# Filter-16.net
KiCad netlist of a schematic drawn in Altium Designer
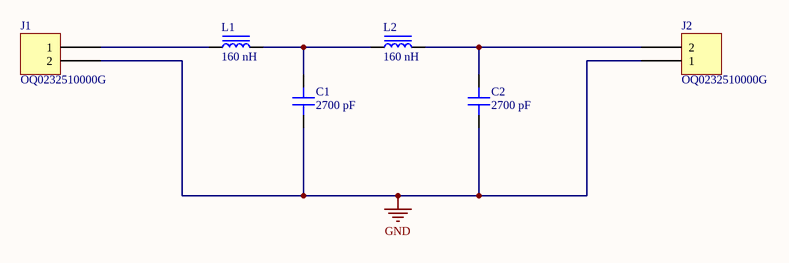
[diagram p0: Filter-16.SchDoc]

(export (version "E")
  (design (tool "Eeschema 10.0.6"))
  (components
    (comp (ref "C1")
      (value "2700 pF")
      (footprint "CAP 0603_1608")
      (description "CAP CER 2700PF 25V NP0 0603")
      (fields (field (name "PART NUMBER") "C0603C272F3GAC7867") (field (name "MANUFACTURER") "KEMET"))
      (libsource (lib "Celestial Altium Library - altium_library") (part "Capacitor"))
    )
    (comp (ref "C2")
      (value "2700 pF")
      (footprint "CAP 0603_1608")
      (description "CAP CER 2700PF 25V NP0 0603")
      (fields (field (name "PART NUMBER") "C0603C272F3GAC7867") (field (name "MANUFACTURER") "KEMET"))
      (libsource (lib "Celestial Altium Library - altium_library") (part "Capacitor"))
    )
    (comp (ref "J1")
      (value "OQ0232510000G")
      (footprint "FCI 06-381-2PIN")
      (description "TERM BLOCK HDR 2POS 90DEG 3.81MM")
      (fields (field (name "MANUFACTURER") "Amphenol Anytek"))
      (libsource (lib "Celestial Altium Library - altium_library") (part "2 Pin"))
    )
    (comp (ref "J2")
      (value "OQ0232510000G")
      (footprint "FCI 06-381-2PIN")
      (description "TERM BLOCK HDR 2POS 90DEG 3.81MM")
      (fields (field (name "MANUFACTURER") "Amphenol Anytek"))
      (libsource (lib "") (part "2 Pin_1"))
    )
    (comp (ref "L1")
      (value "160 nH")
      (footprint "IND 0402_1005 RF WW")
      (description "FIXED IND 160NH 480MA 330MOHM SM")
      (fields
        (field (name "PART NUMBER") "LQW15CNR16J00D")
        (field (name "MANUFACTURER") "Murata Electronics")
      )
      (libsource (lib "Celestial Altium Library - altium_library") (part "Inductor"))
    )
    (comp (ref "L2")
      (value "160 nH")
      (footprint "IND 0402_1005 RF WW")
      (description "FIXED IND 160NH 480MA 330MOHM SM")
      (fields
        (field (name "PART NUMBER") "LQW15CNR16J00D")
        (field (name "MANUFACTURER") "Murata Electronics")
      )
      (libsource (lib "Celestial Altium Library - altium_library") (part "Inductor"))
    )
  )
  (nets
    (net (code "1") (name "GND") (class "Default")
      (node (ref "C1") (pin "1") (pinfunction "1_1") (pintype "passive"))
      (node (ref "C2") (pin "1") (pinfunction "1_1") (pintype "passive"))
      (node (ref "J1") (pin "2") (pinfunction "2_2") (pintype "passive"))
      (node (ref "J2") (pin "1") (pinfunction "1_1") (pintype "passive"))
    )
    (net (code "2") (name "Net-(C1-Pad2)") (class "Default")
      (node (ref "C1") (pin "2") (pinfunction "2_2") (pintype "passive"))
      (node (ref "L1") (pin "2") (pinfunction "2_2") (pintype "passive"))
      (node (ref "L2") (pin "1") (pinfunction "1_1") (pintype "passive"))
    )
    (net (code "3") (name "Net-(C2-Pad2)") (class "Default")
      (node (ref "C2") (pin "2") (pinfunction "2_2") (pintype "passive"))
      (node (ref "J2") (pin "2") (pinfunction "2_2") (pintype "passive"))
      (node (ref "L2") (pin "2") (pinfunction "2_2") (pintype "passive"))
    )
    (net (code "4") (name "Net-(J1-Pad1)") (class "Default")
      (node (ref "J1") (pin "1") (pinfunction "1_1") (pintype "passive"))
      (node (ref "L1") (pin "1") (pinfunction "1_1") (pintype "passive"))
    )
  )
)
